# Relay.net
KiCad netlist of a schematic drawn in Altium Designer
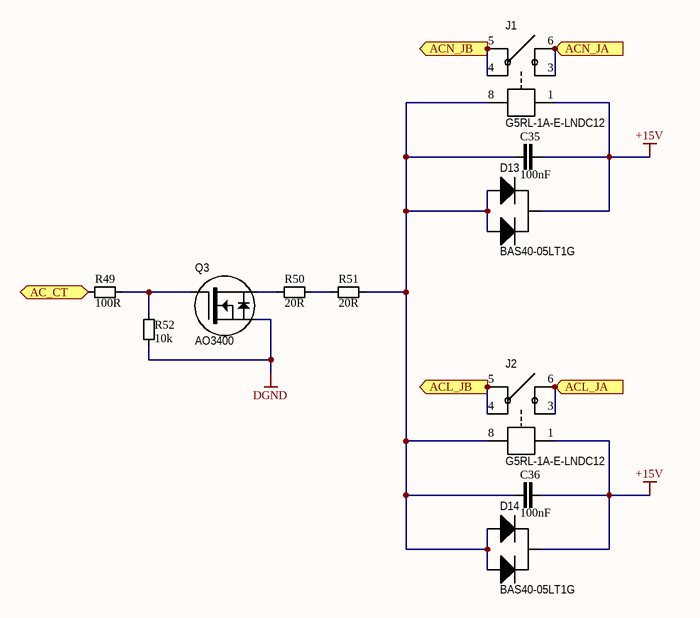
[diagram p0: Relay.SchDoc]

(export (version "E")
  (design (tool "Eeschema 10.0.6"))
  (components
    (comp (ref "C35")
      (value "100nF")
      (footprint "GreenBox:0603-C")
      (description "MLCC 100nF 10% 50V X7R 0603")
      (fields (field (name "Comment") "Cap") (field (name "PUBLISHER") "GreenBox"))
      (libsource (lib "Capacitor") (part "C21C100NK1H0"))
    )
    (comp (ref "C36")
      (value "100nF")
      (footprint "GreenBox:0603-C")
      (description "MLCC 100nF 10% 50V X7R 0603")
      (fields (field (name "Comment") "Cap") (field (name "PUBLISHER") "GreenBox"))
      (libsource (lib "Capacitor") (part "C21C100NK1H0"))
    )
    (comp (ref "D13")
      (value "BAS40-05LT1G")
      (footprint "GreenBox:SOT-23_N")
      (description "Dual Series Schottky Barrier Diode BAS40-05LT1G Vrrm 40V If 0.12A Ir 1uA")
      (fields (field (name "MANUFACTURER") "ON SEMICONDUCTOR") (field (name "PUBLISHER") "GreenBox"))
      (libsource (lib "Diode_Transistor") (part "D842BAS4005O"))
    )
    (comp (ref "D14")
      (value "BAS40-05LT1G")
      (footprint "GreenBox:SOT-23_N")
      (description "Dual Series Schottky Barrier Diode BAS40-05LT1G Vrrm 40V If 0.12A Ir 1uA")
      (fields (field (name "MANUFACTURER") "ON SEMICONDUCTOR") (field (name "PUBLISHER") "GreenBox"))
      (libsource (lib "Diode_Transistor") (part "D842BAS4005O"))
    )
    (comp (ref "J1")
      (value "G5RL-1A-E-LNDC12")
      (footprint "GreenBox:G5RL-1A-E")
      (description "Power/Signal Relay G5RL-1A-E-LNDC12 16A 250VAC 12VDC")
      (fields (field (name "MANUFACTURER") "OMRON") (field (name "PUBLISHER") "GreenBox"))
      (libsource (lib "Relay") (part "JNDZG5RL1122"))
    )
    (comp (ref "J2")
      (value "G5RL-1A-E-LNDC12")
      (footprint "GreenBox:G5RL-1A-E")
      (description "Power/Signal Relay G5RL-1A-E-LNDC12 16A 250VAC 12VDC")
      (fields (field (name "MANUFACTURER") "OMRON") (field (name "PUBLISHER") "GreenBox"))
      (libsource (lib "Relay") (part "JNDZG5RL1122"))
    )
    (comp (ref "Q3")
      (value "AO3400")
      (footprint "GreenBox:SOT-23_N")
      (description "N-Channel MOSFET AO3400 30V 5.8A")
      (fields (field (name "MANUFACTURER") "ALPHA&OMEGA") (field (name "PUBLISHER") "GreenBox"))
      (libsource (lib "MOSFET") (part "QN42AO34000A"))
    )
    (comp (ref "R49")
      (value "100R")
      (footprint "GreenBox:0603-R")
      (description "SMD Resistor 100R 1% 1/10W 0603 100PPM")
      (fields (field (name "Comment") "Res") (field (name "PUBLISHER") "GreenBox"))
      (libsource (lib "Resistor") (part "R11C100RFBF0"))
    )
    (comp (ref "R50")
      (value "20R")
      (footprint "GreenBox:1206-R")
      (description "SMD Resistor 20R 1% 1/4W 1206 100PPM")
      (fields (field (name "Comment") "Res") (field (name "PUBLISHER") "GreenBox"))
      (libsource (lib "Resistor") (part "R11E020RFDF0"))
    )
    (comp (ref "R51")
      (value "20R")
      (footprint "GreenBox:1206-R")
      (description "SMD Resistor 20R 1% 1/4W 1206 100PPM")
      (fields (field (name "Comment") "Res") (field (name "PUBLISHER") "GreenBox"))
      (libsource (lib "Resistor") (part "R11E020RFDF0"))
    )
    (comp (ref "R52")
      (value "10k")
      (footprint "GreenBox:0603-R")
      (description "SMD Resistor 10k 1% 1/10W 0603 100PPM")
      (fields (field (name "Comment") "Res") (field (name "PUBLISHER") "GreenBox"))
      (libsource (lib "Resistor") (part "R11C010KFBF0"))
    )
  )
  (nets
    (net (code "1") (name "+15V") (class "Default")
      (node (ref "C35") (pin "2") (pinfunction "2_2") (pintype "passive"))
      (node (ref "C36") (pin "2") (pinfunction "2_2") (pintype "passive"))
      (node (ref "D13") (pin "3") (pinfunction "3_3") (pintype "passive"))
      (node (ref "D14") (pin "3") (pinfunction "3_3") (pintype "passive"))
      (node (ref "J1") (pin "1") (pinfunction "1_1") (pintype "passive"))
      (node (ref "J2") (pin "1") (pinfunction "1_1") (pintype "passive"))
    )
    (net (code "2") (name "/ACL_JA") (class "Default")
      (node (ref "J2") (pin "3") (pinfunction "3_3") (pintype "passive"))
      (node (ref "J2") (pin "6") (pinfunction "6_6") (pintype "passive"))
    )
    (net (code "3") (name "/ACL_JB") (class "Default")
      (node (ref "J2") (pin "4") (pinfunction "4_4") (pintype "passive"))
      (node (ref "J2") (pin "5") (pinfunction "5_5") (pintype "passive"))
    )
    (net (code "4") (name "/ACN_JA") (class "Default")
      (node (ref "J1") (pin "3") (pinfunction "3_3") (pintype "passive"))
      (node (ref "J1") (pin "6") (pinfunction "6_6") (pintype "passive"))
    )
    (net (code "5") (name "/ACN_JB") (class "Default")
      (node (ref "J1") (pin "4") (pinfunction "4_4") (pintype "passive"))
      (node (ref "J1") (pin "5") (pinfunction "5_5") (pintype "passive"))
    )
    (net (code "6") (name "/AC_CT") (class "Default")
      (node (ref "R49") (pin "1") (pinfunction "1_1") (pintype "passive"))
    )
    (net (code "7") (name "DGND") (class "Default")
      (node (ref "Q3") (pin "2") (pinfunction "S_2") (pintype "passive"))
      (node (ref "R52") (pin "2") (pinfunction "2_2") (pintype "passive"))
    )
    (net (code "8") (name "Net-(C35-Pad1)") (class "Default")
      (node (ref "C35") (pin "1") (pinfunction "1_1") (pintype "passive"))
      (node (ref "C36") (pin "1") (pinfunction "1_1") (pintype "passive"))
      (node (ref "D13") (pin "1") (pinfunction "1_1") (pintype "passive"))
      (node (ref "D13") (pin "2") (pinfunction "2_2") (pintype "passive"))
      (node (ref "D14") (pin "1") (pinfunction "1_1") (pintype "passive"))
      (node (ref "D14") (pin "2") (pinfunction "2_2") (pintype "passive"))
      (node (ref "J1") (pin "8") (pinfunction "8_8") (pintype "passive"))
      (node (ref "J2") (pin "8") (pinfunction "8_8") (pintype "passive"))
      (node (ref "R51") (pin "2") (pinfunction "2_2") (pintype "passive"))
    )
    (net (code "9") (name "Net-(Q3-D)") (class "Default")
      (node (ref "Q3") (pin "3") (pinfunction "D_3") (pintype "passive"))
      (node (ref "R50") (pin "1") (pinfunction "1_1") (pintype "passive"))
    )
    (net (code "10") (name "Net-(Q3-G)") (class "Default")
      (node (ref "Q3") (pin "1") (pinfunction "G_1") (pintype "passive"))
      (node (ref "R49") (pin "2") (pinfunction "2_2") (pintype "passive"))
      (node (ref "R52") (pin "1") (pinfunction "1_1") (pintype "passive"))
    )
    (net (code "11") (name "Net-(R50-Pad2)") (class "Default")
      (node (ref "R50") (pin "2") (pinfunction "2_2") (pintype "passive"))
      (node (ref "R51") (pin "1") (pinfunction "1_1") (pintype "passive"))
    )
  )
)
